# WirelessChargingReceive_V1_0.net
KiCad netlist of a schematic drawn in EasyEDA Pro
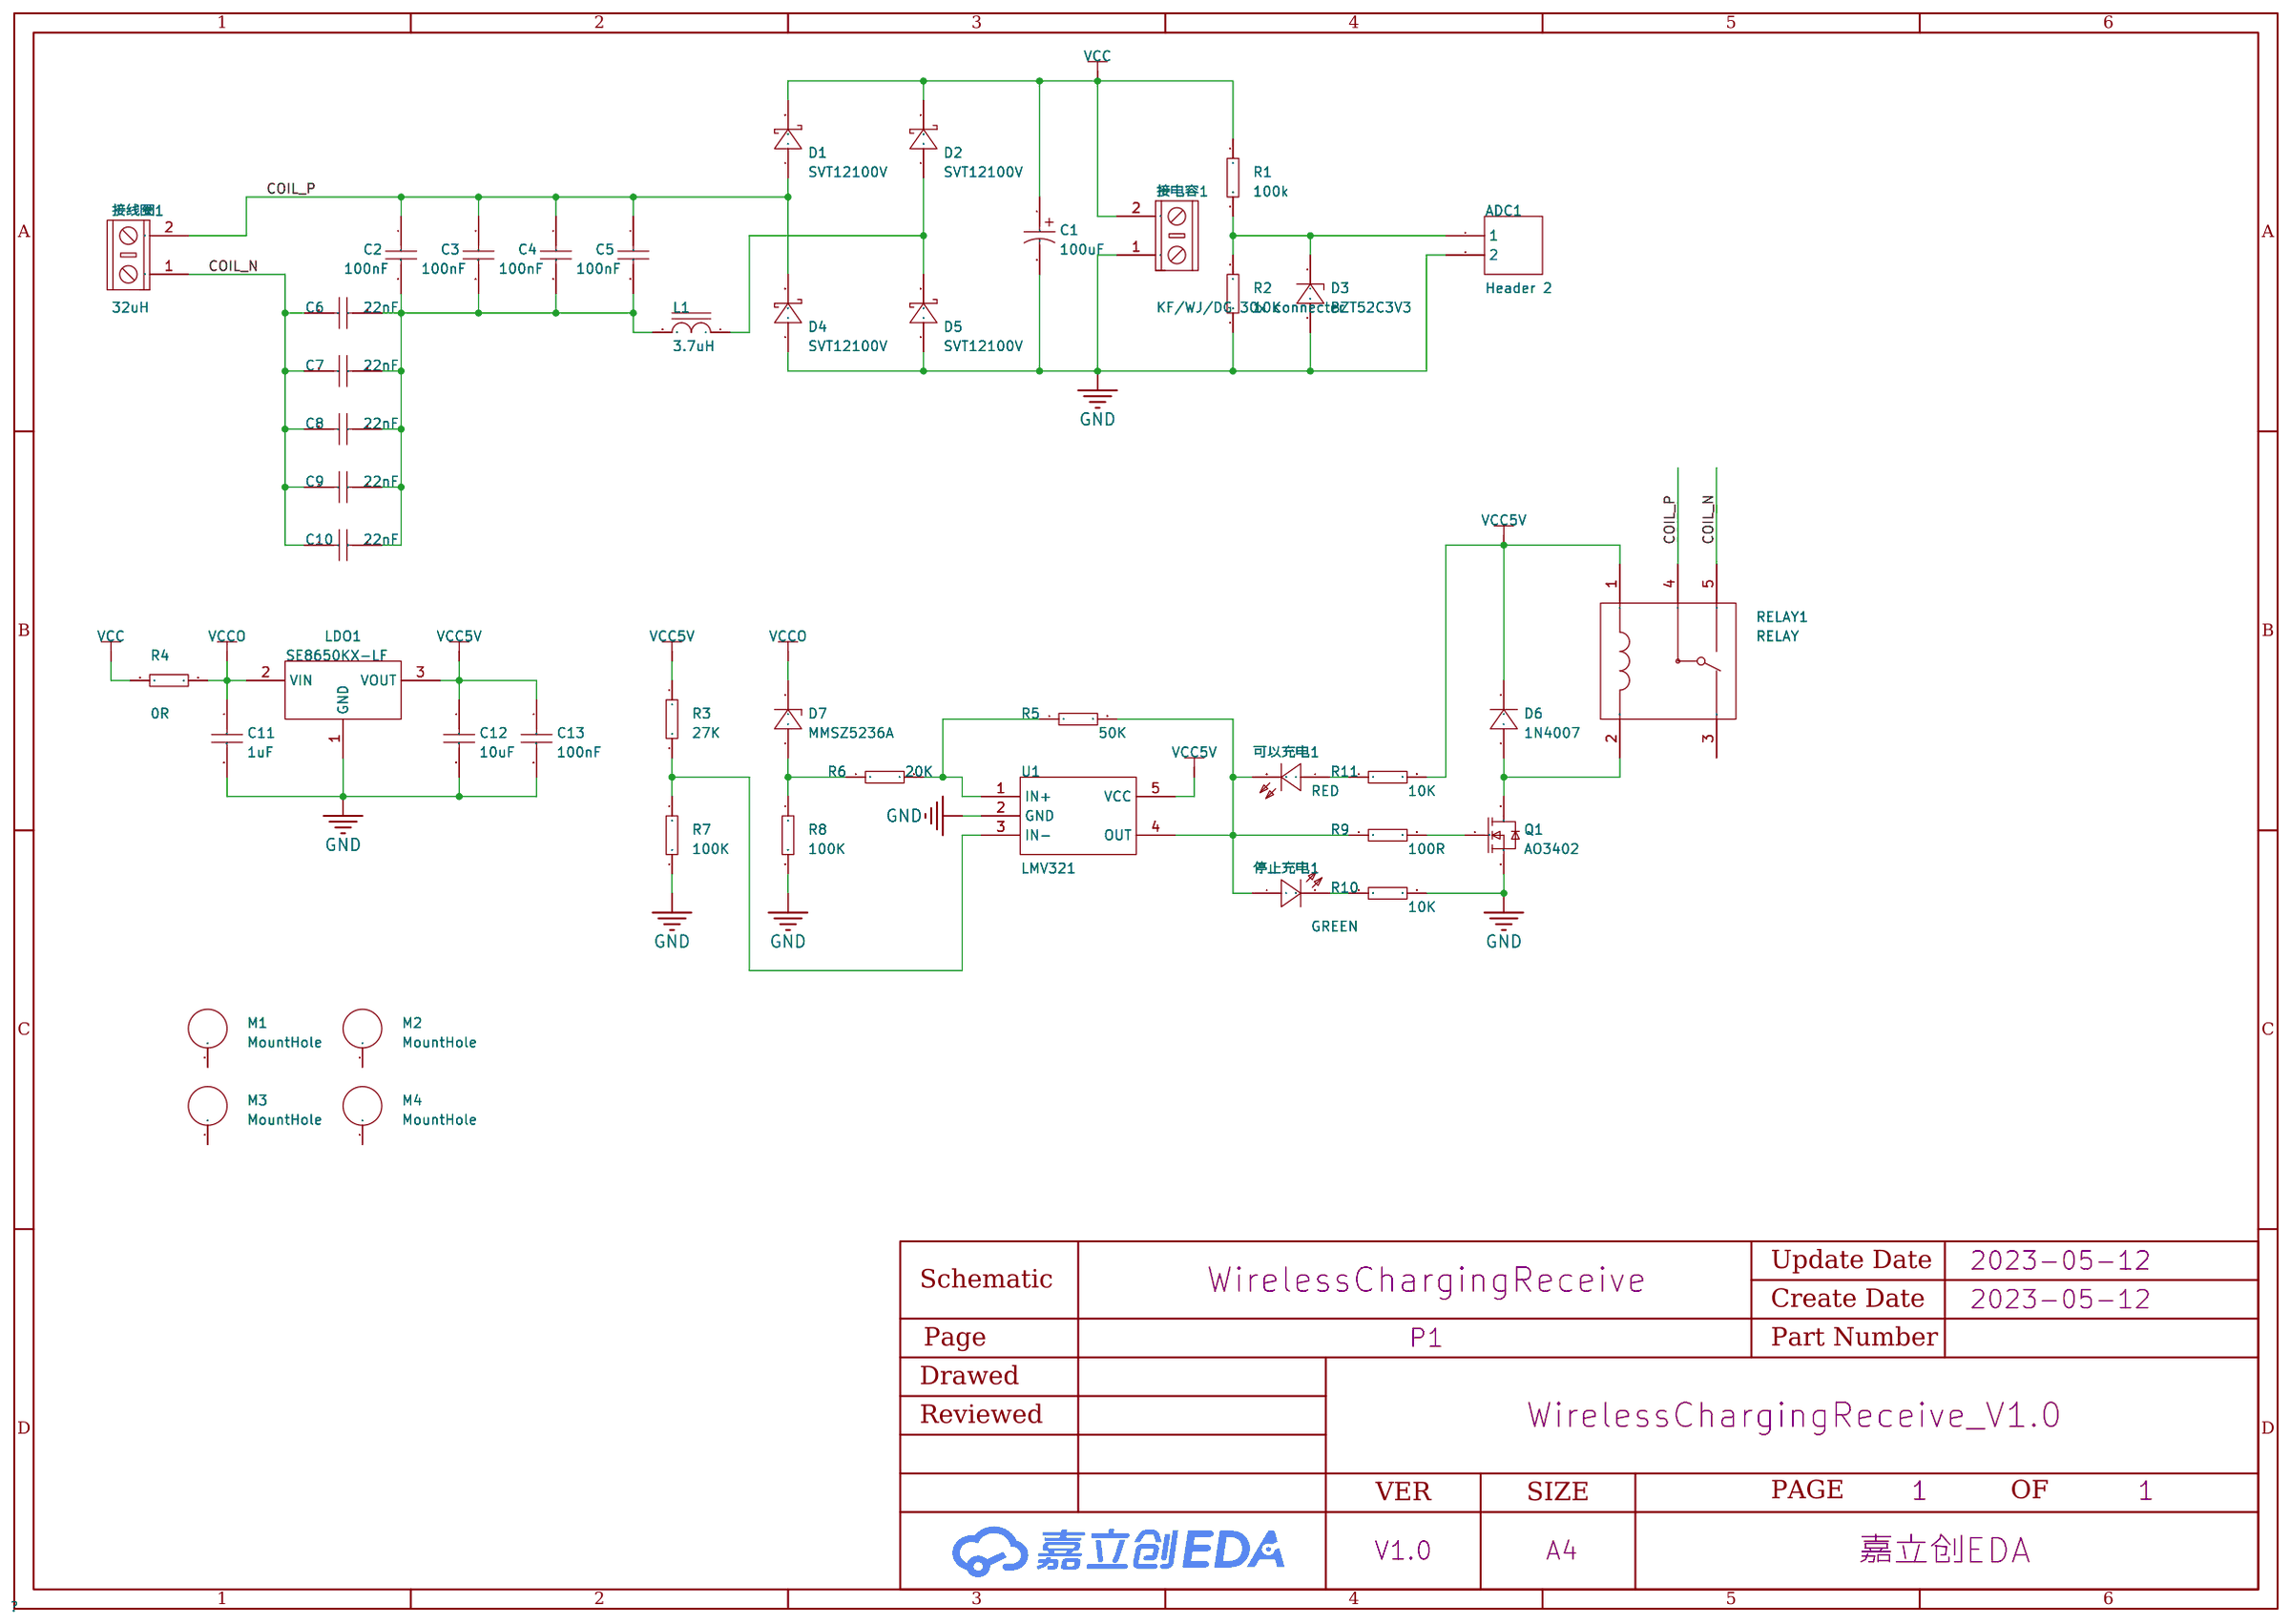
[diagram p0: schematic sheet]

(export (version "E")
  (design (tool "Eeschema 10.0.6"))
  (components
    (comp (ref "ADC1")
      (value "Header 2")
      (footprint "easyedapro:HDR1X2")
      (libsource (lib "easyedapro") (part "Header 2"))
    )
    (comp (ref "C1")
      (value "100uF")
      (footprint "easyedapro:CAPPR5-10X16")
      (libsource (lib "easyedapro") (part "Cap-Elect"))
    )
    (comp (ref "C2")
      (value "100nF")
      (footprint "easyedapro:CAPC3216[1206]S")
      (libsource (lib "easyedapro") (part "Cap-Chip_1"))
    )
    (comp (ref "C3")
      (value "100nF")
      (footprint "easyedapro:CAPC3216[1206]S")
      (libsource (lib "easyedapro") (part "Cap-Chip_1"))
    )
    (comp (ref "C4")
      (value "100nF")
      (footprint "easyedapro:CAPC3216[1206]S")
      (libsource (lib "easyedapro") (part "Cap-Chip_1"))
    )
    (comp (ref "C5")
      (value "100nF")
      (footprint "easyedapro:CAPC3216[1206]S")
      (libsource (lib "easyedapro") (part "Cap-Chip_1"))
    )
    (comp (ref "C6")
      (value "22nF")
      (footprint "easyedapro:CAPC3216[1206]S")
      (libsource (lib "easyedapro") (part "Cap-Chip"))
    )
    (comp (ref "C7")
      (value "22nF")
      (footprint "easyedapro:CAPC3216[1206]S")
      (libsource (lib "easyedapro") (part "Cap-Chip"))
    )
    (comp (ref "C8")
      (value "22nF")
      (footprint "easyedapro:CAPC3216[1206]S")
      (libsource (lib "easyedapro") (part "Cap-Chip"))
    )
    (comp (ref "C9")
      (value "22nF")
      (footprint "easyedapro:CAPC3216[1206]S")
      (libsource (lib "easyedapro") (part "Cap-Chip"))
    )
    (comp (ref "C10")
      (value "22nF")
      (footprint "easyedapro:CAPC3216[1206]S")
      (libsource (lib "easyedapro") (part "Cap-Chip"))
    )
    (comp (ref "C11")
      (value "1uF")
      (footprint "easyedapro:CAPC3216[1206]")
      (libsource (lib "easyedapro") (part "Cap-Chip_2"))
    )
    (comp (ref "C12")
      (value "10uF")
      (footprint "easyedapro:CAPC3216[1206]")
      (libsource (lib "easyedapro") (part "Cap-Chip_3"))
    )
    (comp (ref "C13")
      (value "100nF")
      (footprint "easyedapro:CAPC1608[0603]S-N")
      (libsource (lib "easyedapro") (part "Cap-Chip_4"))
    )
    (comp (ref "D1")
      (value "SVT12100V")
      (footprint "easyedapro:TO-277B")
      (libsource (lib "easyedapro") (part "FM10U100"))
    )
    (comp (ref "D2")
      (value "SVT12100V")
      (footprint "easyedapro:TO-277B")
      (libsource (lib "easyedapro") (part "FM10U100"))
    )
    (comp (ref "D3")
      (value "BZT52C3V3")
      (footprint "easyedapro:SOD-123-L")
      (libsource (lib "easyedapro") (part "Diode Zen"))
    )
    (comp (ref "D4")
      (value "SVT12100V")
      (footprint "easyedapro:TO-277B")
      (libsource (lib "easyedapro") (part "FM10U100"))
    )
    (comp (ref "D5")
      (value "SVT12100V")
      (footprint "easyedapro:TO-277B")
      (libsource (lib "easyedapro") (part "FM10U100"))
    )
    (comp (ref "D6")
      (value "1N4007")
      (footprint "easyedapro:SOD-123-L")
      (libsource (lib "easyedapro") (part "Diode"))
    )
    (comp (ref "D7")
      (value "MMSZ5236A")
      (footprint "easyedapro:SOD-123-L")
      (libsource (lib "easyedapro") (part "Diode Zen_1"))
    )
    (comp (ref "L1")
      (value "3.7uH")
      (footprint "easyedapro:T106-LAY")
      (libsource (lib "easyedapro") (part "Ind-Power"))
    )
    (comp (ref "LDO1")
      (value "SE8650KX-LF")
      (footprint "easyedapro:SOT-89[T0243AA][SC62]")
      (libsource (lib "easyedapro") (part "SE86XXKX-LF"))
    )
    (comp (ref "M1")
      (value "MountHole")
      (footprint "easyedapro:M3-MountHole-Plated")
      (libsource (lib "easyedapro") (part "MountHole"))
    )
    (comp (ref "M2")
      (value "MountHole")
      (footprint "easyedapro:M3-MountHole-Plated")
      (libsource (lib "easyedapro") (part "MountHole"))
    )
    (comp (ref "M3")
      (value "MountHole")
      (footprint "easyedapro:M3-MountHole-Plated")
      (libsource (lib "easyedapro") (part "MountHole"))
    )
    (comp (ref "M4")
      (value "MountHole")
      (footprint "easyedapro:M3-MountHole-Plated")
      (libsource (lib "easyedapro") (part "MountHole"))
    )
    (comp (ref "Q1")
      (value "AO3402")
      (footprint "easyedapro:SOT-23")
      (libsource (lib "easyedapro") (part "AO3400"))
    )
    (comp (ref "R1")
      (value "100K")
      (footprint "easyedapro:RESC1608[0603]S-N")
      (libsource (lib "easyedapro") (part "Res-Chip"))
    )
    (comp (ref "R2")
      (value "10K")
      (footprint "easyedapro:RESC1608[0603]S-N")
      (libsource (lib "easyedapro") (part "Res-Chip_1"))
    )
    (comp (ref "R3")
      (value "27K")
      (footprint "easyedapro:RESC1608[0603]S-N")
      (libsource (lib "easyedapro") (part "Res-Chip_4"))
    )
    (comp (ref "R4")
      (value "0R")
      (footprint "easyedapro:RESC1608[0603]S-N")
      (libsource (lib "easyedapro") (part "Res-Chip_6"))
    )
    (comp (ref "R5")
      (value "50K")
      (footprint "easyedapro:RESC1608[0603]S-N")
      (libsource (lib "easyedapro") (part "Res-Chip_3"))
    )
    (comp (ref "R6")
      (value "20K")
      (footprint "easyedapro:RESC1608[0603]S-N")
      (libsource (lib "easyedapro") (part "Res-Chip_2"))
    )
    (comp (ref "R7")
      (value "100K")
      (footprint "easyedapro:RESC1608[0603]S-N")
      (libsource (lib "easyedapro") (part "Res-Chip"))
    )
    (comp (ref "R8")
      (value "100K")
      (footprint "easyedapro:RESC1608[0603]S-N")
      (libsource (lib "easyedapro") (part "Res-Chip"))
    )
    (comp (ref "R9")
      (value "100R")
      (footprint "easyedapro:RESC1608[0603]S-N")
      (libsource (lib "easyedapro") (part "Res-Chip_5"))
    )
    (comp (ref "R10")
      (value "10K")
      (footprint "easyedapro:RESC1608[0603]S-N")
      (libsource (lib "easyedapro") (part "Res-Chip_1"))
    )
    (comp (ref "R11")
      (value "10K")
      (footprint "easyedapro:RESC1608[0603]S-N")
      (libsource (lib "easyedapro") (part "Res-Chip_1"))
    )
    (comp (ref "RELAY1")
      (value "RELAY")
      (footprint "easyedapro:RELAY-15x10x12")
      (libsource (lib "easyedapro") (part "RELAY"))
    )
    (comp (ref "U1")
      (value "LMV321")
      (footprint "easyedapro:SOT-23-5")
      (libsource (lib "easyedapro") (part "LM321"))
    )
    (comp (ref "停止充电1")
      (value "GREEN")
      (footprint "easyedapro:LEDC1608(0603)-L")
      (libsource (lib "easyedapro") (part "LED Chip Green"))
    )
    (comp (ref "可以充电1")
      (value "RED")
      (footprint "easyedapro:LEDC1608(0603)-L")
      (libsource (lib "easyedapro") (part "LED Chip Red"))
    )
    (comp (ref "接电容1")
      (value "KF/WJ/DG 30x connecter")
      (footprint "easyedapro:KF/WJ/DG 301-2p-5.0mm")
      (libsource (lib "easyedapro") (part "KF/WJ/DG 30x"))
    )
    (comp (ref "接线圈1")
      (value "32uH")
      (footprint "easyedapro:KF/WJ/DG 301-2p-5.0mm")
      (libsource (lib "easyedapro") (part "KF/WJ/DG 30x"))
    )
  )
  (nets
    (net (code "1") (name "/COIL_N") (class "Default")
      (node (ref "C10") (pin "1") (pinfunction "1_1") (pintype "input"))
      (node (ref "C6") (pin "1") (pinfunction "1_1") (pintype "input"))
      (node (ref "C7") (pin "1") (pinfunction "1_1") (pintype "input"))
      (node (ref "C8") (pin "1") (pinfunction "1_1") (pintype "input"))
      (node (ref "C9") (pin "1") (pinfunction "1_1") (pintype "input"))
      (node (ref "RELAY1") (pin "5") (pinfunction "5_5") (pintype "input"))
      (node (ref "接线圈1") (pin "1") (pinfunction "1_1") (pintype "input"))
    )
    (net (code "2") (name "/COIL_P") (class "Default")
      (node (ref "C2") (pin "1") (pinfunction "1_1") (pintype "input"))
      (node (ref "C3") (pin "1") (pinfunction "1_1") (pintype "input"))
      (node (ref "C4") (pin "1") (pinfunction "1_1") (pintype "input"))
      (node (ref "C5") (pin "1") (pinfunction "1_1") (pintype "input"))
      (node (ref "D1") (pin "1") (pinfunction "1_1") (pintype "input"))
      (node (ref "D4") (pin "2") (pinfunction "2_2") (pintype "input"))
      (node (ref "RELAY1") (pin "4") (pinfunction "4_4") (pintype "input"))
      (node (ref "接线圈1") (pin "2") (pinfunction "2_2") (pintype "input"))
    )
    (net (code "3") (name "GND") (class "Default")
      (node (ref "ADC1") (pin "2") (pinfunction "2_2") (pintype "input"))
      (node (ref "C1") (pin "2") (pinfunction "2_2") (pintype "input"))
      (node (ref "C11") (pin "2") (pinfunction "2_2") (pintype "input"))
      (node (ref "C12") (pin "2") (pinfunction "2_2") (pintype "input"))
      (node (ref "C13") (pin "2") (pinfunction "2_2") (pintype "input"))
      (node (ref "D3") (pin "A") (pinfunction "A_A") (pintype "input"))
      (node (ref "D4") (pin "1") (pinfunction "1_1") (pintype "input"))
      (node (ref "D5") (pin "1") (pinfunction "1_1") (pintype "input"))
      (node (ref "LDO1") (pin "1") (pinfunction "GND_1") (pintype "input"))
      (node (ref "Q1") (pin "2") (pinfunction "S_2") (pintype "input"))
      (node (ref "R10") (pin "2") (pinfunction "2_2") (pintype "input"))
      (node (ref "R2") (pin "2") (pinfunction "2_2") (pintype "input"))
      (node (ref "R7") (pin "2") (pinfunction "2_2") (pintype "input"))
      (node (ref "R8") (pin "2") (pinfunction "2_2") (pintype "input"))
      (node (ref "U1") (pin "2") (pinfunction "GND_2") (pintype "input"))
      (node (ref "接电容1") (pin "1") (pinfunction "1_1") (pintype "input"))
    )
    (net (code "4") (name "Net-(ADC1-Pad1)") (class "Default")
      (node (ref "ADC1") (pin "1") (pinfunction "1_1") (pintype "input"))
      (node (ref "D3") (pin "K") (pinfunction "K_K") (pintype "input"))
      (node (ref "R1") (pin "2") (pinfunction "2_2") (pintype "input"))
      (node (ref "R2") (pin "1") (pinfunction "1_1") (pintype "input"))
    )
    (net (code "5") (name "Net-(C10-Pad2)") (class "Default")
      (node (ref "C10") (pin "2") (pinfunction "2_2") (pintype "input"))
      (node (ref "C2") (pin "2") (pinfunction "2_2") (pintype "input"))
      (node (ref "C3") (pin "2") (pinfunction "2_2") (pintype "input"))
      (node (ref "C4") (pin "2") (pinfunction "2_2") (pintype "input"))
      (node (ref "C5") (pin "2") (pinfunction "2_2") (pintype "input"))
      (node (ref "C6") (pin "2") (pinfunction "2_2") (pintype "input"))
      (node (ref "C7") (pin "2") (pinfunction "2_2") (pintype "input"))
      (node (ref "C8") (pin "2") (pinfunction "2_2") (pintype "input"))
      (node (ref "C9") (pin "2") (pinfunction "2_2") (pintype "input"))
      (node (ref "L1") (pin "2") (pinfunction "2_2") (pintype "input"))
    )
    (net (code "6") (name "Net-(D2-Pad1)") (class "Default")
      (node (ref "D2") (pin "1") (pinfunction "1_1") (pintype "input"))
      (node (ref "D5") (pin "2") (pinfunction "2_2") (pintype "input"))
      (node (ref "L1") (pin "1") (pinfunction "1_1") (pintype "input"))
    )
    (net (code "7") (name "Net-(D7-PadA)") (class "Default")
      (node (ref "D7") (pin "A") (pinfunction "A_A") (pintype "input"))
      (node (ref "R6") (pin "1") (pinfunction "1_1") (pintype "input"))
      (node (ref "R8") (pin "1") (pinfunction "1_1") (pintype "input"))
    )
    (net (code "8") (name "Net-(Q1-D)") (class "Default")
      (node (ref "D6") (pin "A") (pinfunction "A_A") (pintype "input"))
      (node (ref "Q1") (pin "3") (pinfunction "D_3") (pintype "input"))
      (node (ref "RELAY1") (pin "2") (pinfunction "2_2") (pintype "input"))
    )
    (net (code "9") (name "Net-(Q1-G)") (class "Default")
      (node (ref "Q1") (pin "1") (pinfunction "G_1") (pintype "input"))
      (node (ref "R9") (pin "2") (pinfunction "2_2") (pintype "input"))
    )
    (net (code "10") (name "Net-(R10-Pad1)") (class "Default")
      (node (ref "R10") (pin "1") (pinfunction "1_1") (pintype "input"))
      (node (ref "停止充电1") (pin "C") (pinfunction "C_C") (pintype "input"))
    )
    (net (code "11") (name "Net-(R11-Pad1)") (class "Default")
      (node (ref "R11") (pin "1") (pinfunction "1_1") (pintype "input"))
      (node (ref "可以充电1") (pin "A") (pinfunction "A_A") (pintype "input"))
    )
    (net (code "12") (name "Net-(U1-IN+)") (class "Default")
      (node (ref "R5") (pin "1") (pinfunction "1_1") (pintype "input"))
      (node (ref "R6") (pin "2") (pinfunction "2_2") (pintype "input"))
      (node (ref "U1") (pin "1") (pinfunction "IN+_1") (pintype "input"))
    )
    (net (code "13") (name "Net-(U1-IN-)") (class "Default")
      (node (ref "R3") (pin "2") (pinfunction "2_2") (pintype "input"))
      (node (ref "R7") (pin "1") (pinfunction "1_1") (pintype "input"))
      (node (ref "U1") (pin "3") (pinfunction "IN-_3") (pintype "input"))
    )
    (net (code "14") (name "Net-(U1-OUT)") (class "Default")
      (node (ref "R5") (pin "2") (pinfunction "2_2") (pintype "input"))
      (node (ref "R9") (pin "1") (pinfunction "1_1") (pintype "input"))
      (node (ref "U1") (pin "4") (pinfunction "OUT_4") (pintype "input"))
      (node (ref "停止充电1") (pin "A") (pinfunction "A_A") (pintype "input"))
      (node (ref "可以充电1") (pin "C") (pinfunction "C_C") (pintype "input"))
    )
    (net (code "15") (name "VCC") (class "Default")
      (node (ref "C1") (pin "1") (pinfunction "1_1") (pintype "input"))
      (node (ref "D1") (pin "2") (pinfunction "2_2") (pintype "input"))
      (node (ref "D2") (pin "2") (pinfunction "2_2") (pintype "input"))
      (node (ref "R1") (pin "1") (pinfunction "1_1") (pintype "input"))
      (node (ref "R4") (pin "1") (pinfunction "1_1") (pintype "input"))
      (node (ref "接电容1") (pin "2") (pinfunction "2_2") (pintype "input"))
    )
    (net (code "16") (name "VCC5V") (class "Default")
      (node (ref "C12") (pin "1") (pinfunction "1_1") (pintype "input"))
      (node (ref "C13") (pin "1") (pinfunction "1_1") (pintype "input"))
      (node (ref "D6") (pin "K") (pinfunction "K_K") (pintype "input"))
      (node (ref "LDO1") (pin "3") (pinfunction "VOUT_3") (pintype "input"))
      (node (ref "R11") (pin "2") (pinfunction "2_2") (pintype "input"))
      (node (ref "R3") (pin "1") (pinfunction "1_1") (pintype "input"))
      (node (ref "RELAY1") (pin "1") (pinfunction "1_1") (pintype "input"))
      (node (ref "U1") (pin "5") (pinfunction "VCC_5") (pintype "input"))
    )
    (net (code "17") (name "VCCO") (class "Default")
      (node (ref "C11") (pin "1") (pinfunction "1_1") (pintype "input"))
      (node (ref "D7") (pin "K") (pinfunction "K_K") (pintype "input"))
      (node (ref "LDO1") (pin "2") (pinfunction "VIN_2") (pintype "input"))
      (node (ref "R4") (pin "2") (pinfunction "2_2") (pintype "input"))
    )
    (net (code "18") (name "unconnected-(M1-Pad1)") (class "Default")
      (node (ref "M1") (pin "1") (pinfunction "1_1") (pintype "input"))
    )
    (net (code "19") (name "unconnected-(M2-Pad1)") (class "Default")
      (node (ref "M2") (pin "1") (pinfunction "1_1") (pintype "input"))
    )
    (net (code "20") (name "unconnected-(M3-Pad1)") (class "Default")
      (node (ref "M3") (pin "1") (pinfunction "1_1") (pintype "input"))
    )
    (net (code "21") (name "unconnected-(M4-Pad1)") (class "Default")
      (node (ref "M4") (pin "1") (pinfunction "1_1") (pintype "input"))
    )
    (net (code "22") (name "unconnected-(RELAY1-Pad3)") (class "Default")
      (node (ref "RELAY1") (pin "3") (pinfunction "3_3") (pintype "input"))
    )
  )
)
